# PSPS_AVNC_SRD_power-2020-10-23_FABRICATE.net
KiCad netlist of a schematic drawn in EAGLE
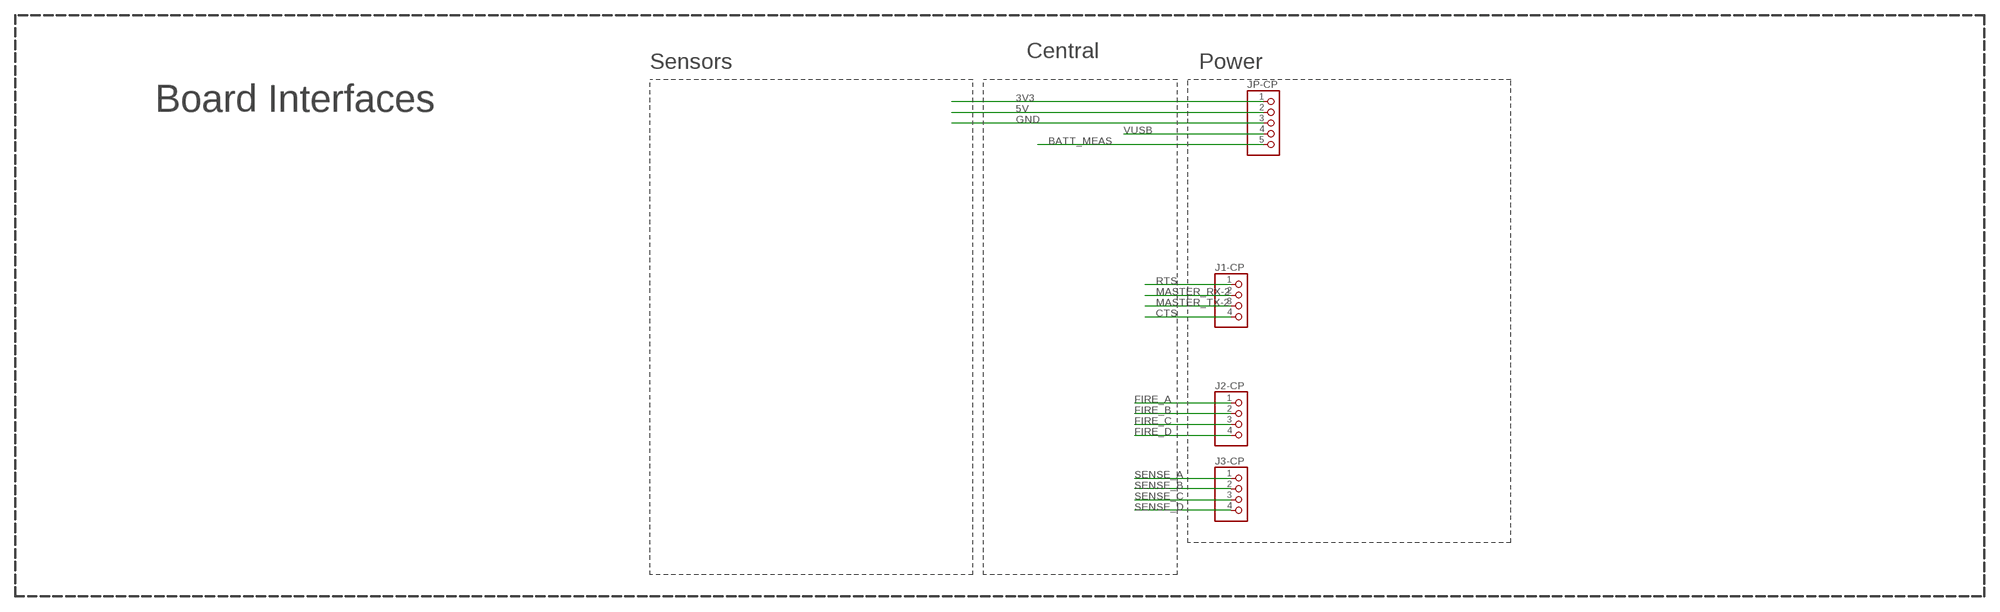
[diagram p0: schematic, sheet 1, part 1 of 3]
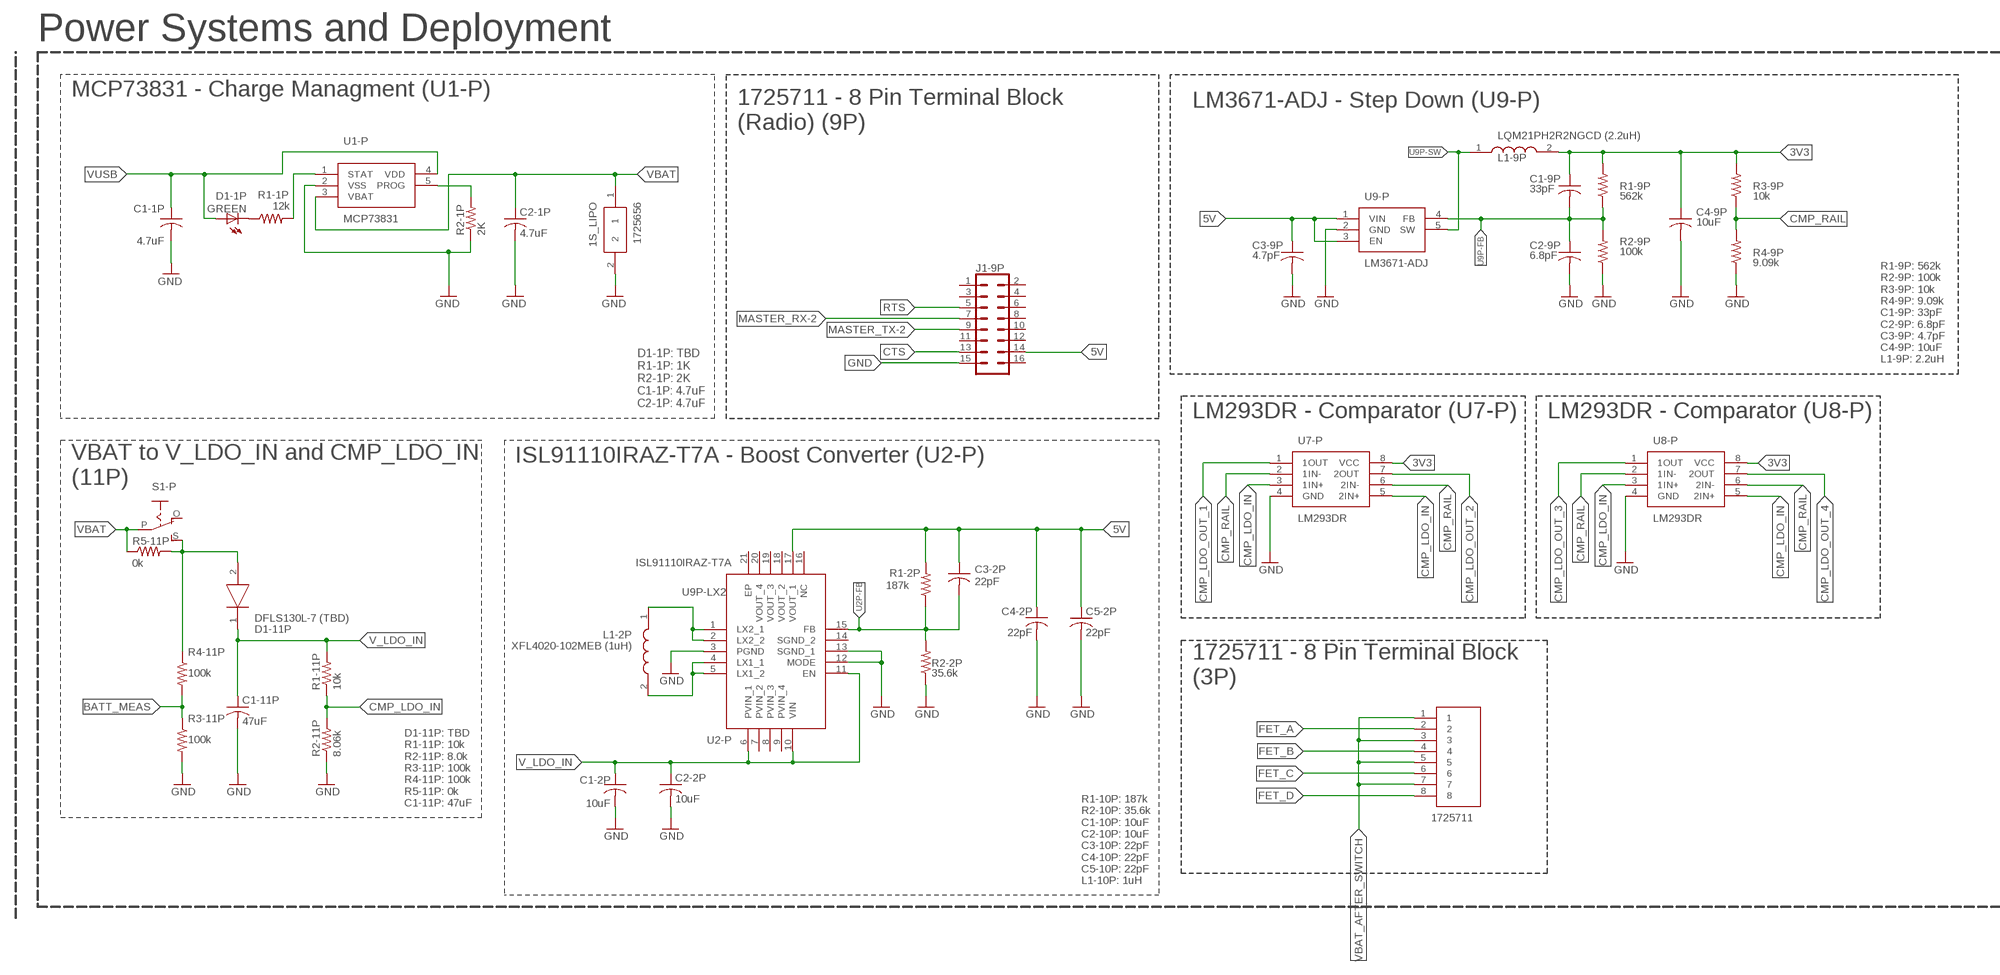
[diagram p1: schematic, sheet 1, part 2 of 3]
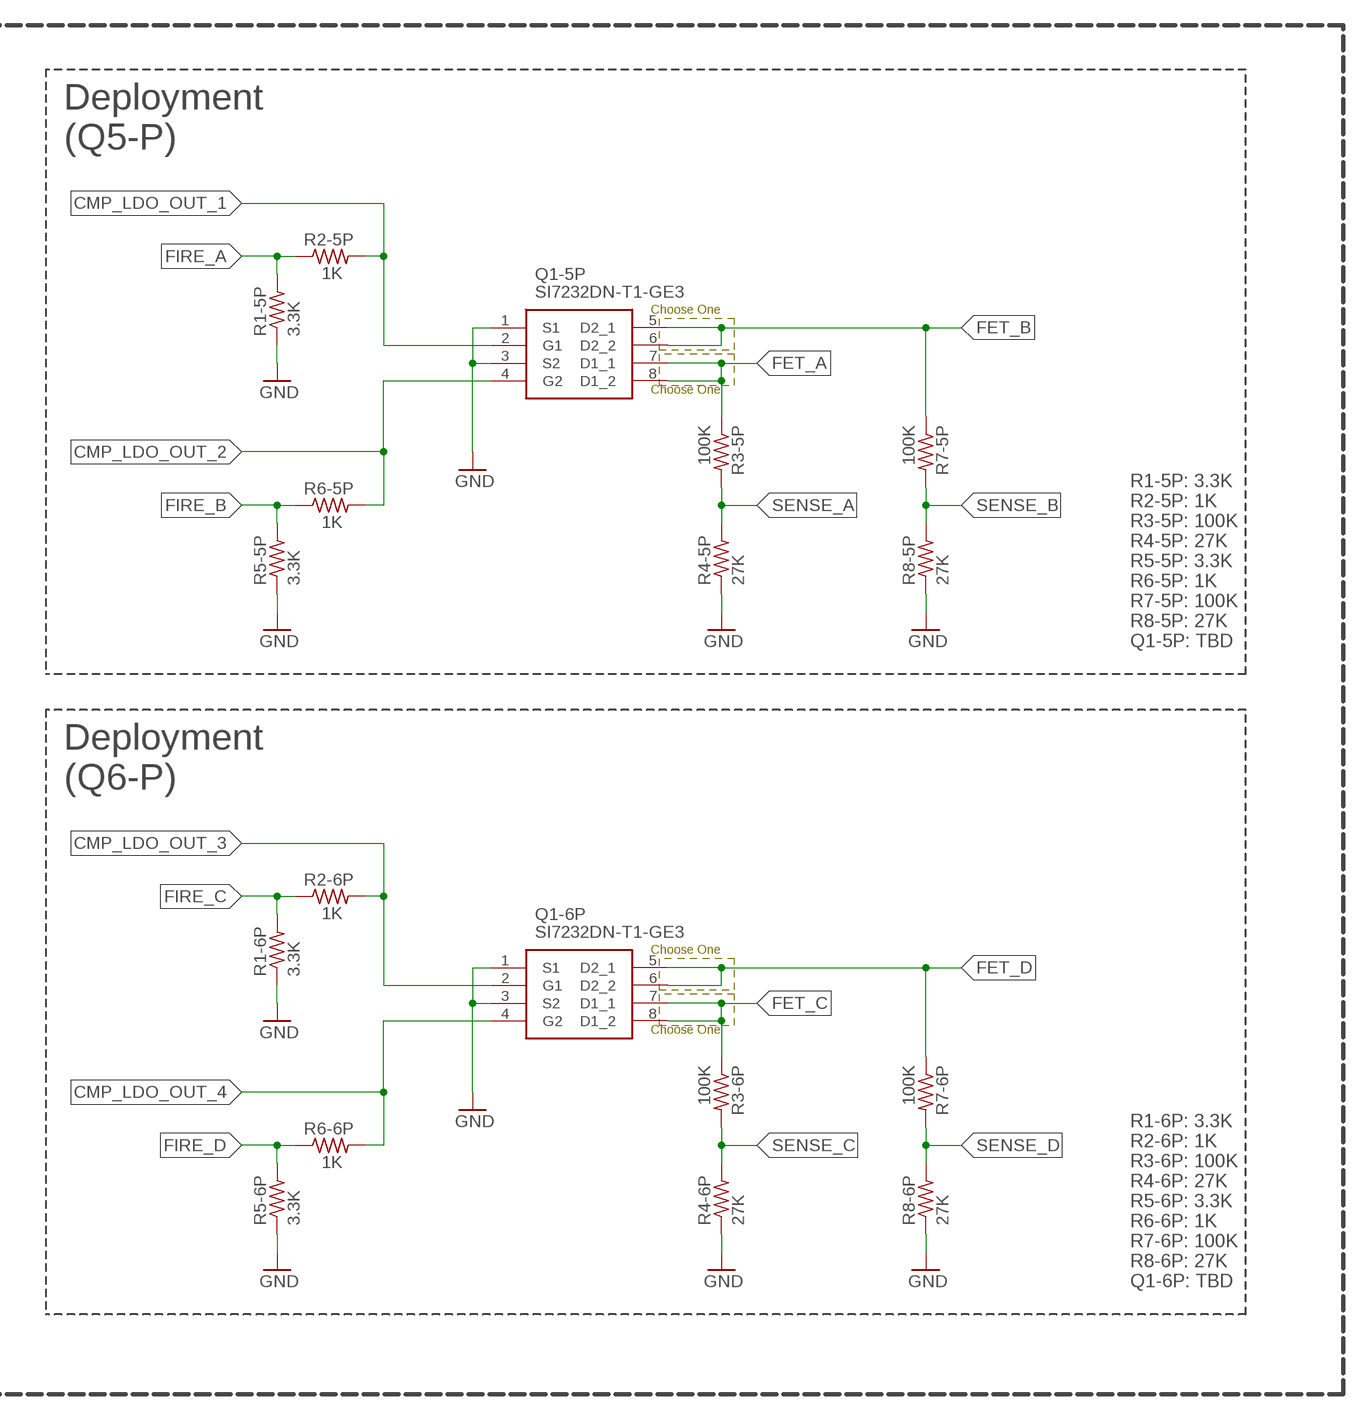
[diagram p2: schematic, sheet 1, part 3 of 3]

(export (version "E")
  (design (tool "Eeschema 10.0.6"))
  (components
    (comp (ref "1S_LIPO")
      (value "1725656")
      (footprint "eagle-import:1725656")
      (fields (field (name "MOUSER_PART_NUMBER") "651-1725656"))
      (libsource (lib "eagle-import") (part "1725656"))
    )
    (comp (ref "C1-1P")
      (value "4.7uF")
      (footprint "eagle-import:C0805")
      (libsource (lib "eagle-import") (part "resistor_348_C-USC0805"))
    )
    (comp (ref "C1-2P")
      (value "10uF")
      (footprint "eagle-import:C0805")
      (libsource (lib "eagle-import") (part "resistor_348_C-USC0805"))
    )
    (comp (ref "C1-9P")
      (value "33pF")
      (footprint "eagle-import:C0805")
      (libsource (lib "eagle-import") (part "resistor_348_C-USC0805"))
    )
    (comp (ref "C1-11P")
      (value "47uF")
      (footprint "eagle-import:C0805")
      (libsource (lib "eagle-import") (part "resistor_348_C-USC0805"))
    )
    (comp (ref "C2-1P")
      (value "4.7uF")
      (footprint "eagle-import:C0805")
      (libsource (lib "eagle-import") (part "resistor_348_C-USC0805"))
    )
    (comp (ref "C2-2P")
      (value "10uF")
      (footprint "eagle-import:C0805")
      (libsource (lib "eagle-import") (part "C-USC0805"))
    )
    (comp (ref "C2-9P")
      (value "6.8pF")
      (footprint "eagle-import:C0805")
      (libsource (lib "eagle-import") (part "resistor_348_C-USC0805"))
    )
    (comp (ref "C3-2P")
      (value "22pF")
      (footprint "eagle-import:C0805")
      (libsource (lib "eagle-import") (part "resistor_348_C-USC0805"))
    )
    (comp (ref "C3-9P")
      (value "4.7pF")
      (footprint "eagle-import:C0805")
      (libsource (lib "eagle-import") (part "resistor_348_C-USC0805"))
    )
    (comp (ref "C4-2P")
      (value "22pF")
      (footprint "eagle-import:C0805")
      (fields (field (name "SPICEPREFIX") "C"))
      (libsource (lib "eagle-import") (part "resistor_348_C-USC0805"))
    )
    (comp (ref "C4-9P")
      (value "10uF")
      (footprint "eagle-import:C0805")
      (libsource (lib "eagle-import") (part "resistor_348_C-USC0805"))
    )
    (comp (ref "C5-2P")
      (value "22pF")
      (footprint "eagle-import:C0805")
      (libsource (lib "eagle-import") (part "C-USC0805"))
    )
    (comp (ref "D1-1P")
      (value "GREEN")
      (footprint "eagle-import:CHIPLED_0805")
      (libsource (lib "eagle-import") (part "LEDCHIPLED_0805"))
    )
    (comp (ref "D1-11P")
      (value "DFLS130L-7 (TBD)")
      (footprint "eagle-import:POWERDI_123")
      (fields
        (field (name "MANUFACTURER_PART_NUMBER") "DFLS130L-7")
        (field (name "MOUSER_PART_NUMBER") "621-DFLS130L")
      )
      (libsource (lib "eagle-import") (part "DFLS130L-7"))
    )
    (comp (ref "J1-9P")
      (value "CONN_08X2")
      (footprint "eagle-import:2X8")
      (libsource (lib "eagle-import") (part "CONN_08X2"))
    )
    (comp (ref "J1-CP")
      (value "PINHD-1X4")
      (footprint "eagle-import:1X04")
      (libsource (lib "eagle-import") (part "PINHD-1X4"))
    )
    (comp (ref "J2-CP")
      (value "PINHD-1X4")
      (footprint "eagle-import:1X04")
      (libsource (lib "eagle-import") (part "PINHD-1X4"))
    )
    (comp (ref "J2-P")
      (value "1725711")
      (footprint "eagle-import:1725711")
      (fields (field (name "MOUSER_PART_NUMBER") "651-1725711"))
      (libsource (lib "eagle-import") (part "1725711"))
    )
    (comp (ref "J3-CP")
      (value "PINHD-1X4")
      (footprint "eagle-import:1X04")
      (libsource (lib "eagle-import") (part "PINHD-1X4"))
    )
    (comp (ref "JP-CP")
      (value "PINHD-1X5")
      (footprint "eagle-import:1X05")
      (libsource (lib "eagle-import") (part "PINHD-1X5"))
    )
    (comp (ref "L1-2P")
      (value "XFL4020-102MEB (1uH)")
      (footprint "eagle-import:XFL4020")
      (fields
        (field (name "MANUFACTURER_PART_NUMBER") "XFL4020-102MEB")
        (field (name "MOUSER_PART_NUMBER") "994-XFL4020-102MEB")
      )
      (libsource (lib "eagle-import") (part "XFL4020-102MEB"))
    )
    (comp (ref "L1-9P")
      (value "LQM21PH2R2NGCD (2.2uH)")
      (footprint "eagle-import:INDC2012X100N")
      (fields
        (field (name "MANUFACTURER_PART_NUMBER") "LQM21PH2R2NGCD")
        (field (name "MOUSER_PART_NUMBER") "81-LQM21PH2R2NGCD")
      )
      (libsource (lib "eagle-import") (part "LQM21PH2R2NGCD"))
    )
    (comp (ref "Q1-5P")
      (value "SI7232DN-T1-GE3")
      (footprint "eagle-import:POWERPAK-1212-8")
      (fields (field (name "MOUSER_PART_NUMBER") "781-SI7232DN-GE3"))
      (libsource (lib "eagle-import") (part "SI7232DN-T1-GE3"))
    )
    (comp (ref "Q1-6P")
      (value "SI7232DN-T1-GE3")
      (footprint "eagle-import:POWERPAK-1212-8")
      (fields (field (name "MOUSER_PART_NUMBER") "781-SI7232DN-GE3"))
      (libsource (lib "eagle-import") (part "SI7232DN-T1-GE3"))
    )
    (comp (ref "R1-1P")
      (value "12k")
      (footprint "eagle-import:R0805")
      (libsource (lib "eagle-import") (part "resistor_348_R-US_R0805"))
    )
    (comp (ref "R1-2P")
      (value "187k")
      (footprint "eagle-import:R0805")
      (libsource (lib "eagle-import") (part "resistor_348_R-US_R0805"))
    )
    (comp (ref "R1-5P")
      (value "3.3K")
      (footprint "eagle-import:M0805")
      (libsource (lib "eagle-import") (part "rcl_334_R-US_M0805"))
    )
    (comp (ref "R1-6P")
      (value "3.3K")
      (footprint "eagle-import:M0805")
      (libsource (lib "eagle-import") (part "rcl_334_R-US_M0805"))
    )
    (comp (ref "R1-9P")
      (value "562k")
      (footprint "eagle-import:R0805")
      (libsource (lib "eagle-import") (part "resistor_348_R-US_R0805"))
    )
    (comp (ref "R1-11P")
      (value "10k")
      (footprint "eagle-import:R0805")
      (libsource (lib "eagle-import") (part "resistor_348_R-US_R0805"))
    )
    (comp (ref "R2-1P")
      (value "2K")
      (footprint "eagle-import:R0805")
      (libsource (lib "eagle-import") (part "resistor_348_R-US_R0805"))
    )
    (comp (ref "R2-2P")
      (value "35.6k")
      (footprint "eagle-import:R0805")
      (libsource (lib "eagle-import") (part "resistor_348_R-US_R0805"))
    )
    (comp (ref "R2-5P")
      (value "1K")
      (footprint "eagle-import:M0805")
      (libsource (lib "eagle-import") (part "rcl_334_R-US_M0805"))
    )
    (comp (ref "R2-6P")
      (value "1K")
      (footprint "eagle-import:M0805")
      (libsource (lib "eagle-import") (part "rcl_334_R-US_M0805"))
    )
    (comp (ref "R2-9P")
      (value "100k")
      (footprint "eagle-import:R0805")
      (libsource (lib "eagle-import") (part "resistor_348_R-US_R0805"))
    )
    (comp (ref "R2-11P")
      (value "8.06k")
      (footprint "eagle-import:R0805")
      (libsource (lib "eagle-import") (part "resistor_348_R-US_R0805"))
    )
    (comp (ref "R3-5P")
      (value "100K")
      (footprint "eagle-import:M0805")
      (libsource (lib "eagle-import") (part "rcl_334_R-US_M0805"))
    )
    (comp (ref "R3-6P")
      (value "100K")
      (footprint "eagle-import:M0805")
      (libsource (lib "eagle-import") (part "rcl_334_R-US_M0805"))
    )
    (comp (ref "R3-9P")
      (value "10k")
      (footprint "eagle-import:R0805")
      (libsource (lib "eagle-import") (part "resistor_348_R-US_R0805"))
    )
    (comp (ref "R3-11P")
      (value "100k")
      (footprint "eagle-import:R0805")
      (libsource (lib "eagle-import") (part "R-US_R0805"))
    )
    (comp (ref "R4-5P")
      (value "27K")
      (footprint "eagle-import:M0805")
      (libsource (lib "eagle-import") (part "rcl_334_R-US_M0805"))
    )
    (comp (ref "R4-6P")
      (value "27K")
      (footprint "eagle-import:M0805")
      (libsource (lib "eagle-import") (part "rcl_334_R-US_M0805"))
    )
    (comp (ref "R4-9P")
      (value "9.09k")
      (footprint "eagle-import:R0805")
      (libsource (lib "eagle-import") (part "resistor_348_R-US_R0805"))
    )
    (comp (ref "R4-11P")
      (value "100k")
      (footprint "eagle-import:R0805")
      (libsource (lib "eagle-import") (part "R-US_R0805"))
    )
    (comp (ref "R5-5P")
      (value "3.3K")
      (footprint "eagle-import:M0805")
      (libsource (lib "eagle-import") (part "rcl_334_R-US_M0805"))
    )
    (comp (ref "R5-6P")
      (value "3.3K")
      (footprint "eagle-import:M0805")
      (libsource (lib "eagle-import") (part "rcl_334_R-US_M0805"))
    )
    (comp (ref "R5-11P")
      (value "0k")
      (footprint "eagle-import:R0805")
      (libsource (lib "eagle-import") (part "R-US_R0805"))
    )
    (comp (ref "R6-5P")
      (value "1K")
      (footprint "eagle-import:M0805")
      (libsource (lib "eagle-import") (part "rcl_334_R-US_M0805"))
    )
    (comp (ref "R6-6P")
      (value "1K")
      (footprint "eagle-import:M0805")
      (libsource (lib "eagle-import") (part "rcl_334_R-US_M0805"))
    )
    (comp (ref "R7-5P")
      (value "100K")
      (footprint "eagle-import:M0805")
      (libsource (lib "eagle-import") (part "rcl_334_R-US_M0805"))
    )
    (comp (ref "R7-6P")
      (value "100K")
      (footprint "eagle-import:M0805")
      (libsource (lib "eagle-import") (part "rcl_334_R-US_M0805"))
    )
    (comp (ref "R8-5P")
      (value "27K")
      (footprint "eagle-import:M0805")
      (libsource (lib "eagle-import") (part "rcl_334_R-US_M0805"))
    )
    (comp (ref "R8-6P")
      (value "27K")
      (footprint "eagle-import:M0805")
      (libsource (lib "eagle-import") (part "rcl_334_R-US_M0805"))
    )
    (comp (ref "S1-P")
      (value "EG1218S")
      (footprint "eagle-import:EG1218")
      (libsource (lib "eagle-import") (part "EG1218S"))
    )
    (comp (ref "U1-P")
      (value "MCP73831")
      (footprint "eagle-import:SOT95P270X145-5N")
      (fields
        (field (name "MANUFACTURER_PART_NUMBER") "MCP73831T-2ACI/OT")
        (field (name "MOUSER_PART_NUMBER") "579-MCP73831T-2ACIOT")
      )
      (libsource (lib "eagle-import") (part "MCP73831T-2ACI_OT"))
    )
    (comp (ref "U2-P")
      (value "ISL91110IRAZ-T7A")
      (footprint "eagle-import:QFN50P400X400X100-21N")
      (libsource (lib "eagle-import") (part "ISL91110IRAZ-T7A"))
    )
    (comp (ref "U7-P")
      (value "LM293DR")
      (footprint "eagle-import:SOIC127P600X175-8N")
      (fields (field (name "MOUSER_PART_NUMBER") "595-LM293DR"))
      (libsource (lib "eagle-import") (part "LM293DR"))
    )
    (comp (ref "U8-P")
      (value "LM293DR")
      (footprint "eagle-import:SOIC127P600X175-8N")
      (fields (field (name "MOUSER_PART_NUMBER") "595-LM293DR"))
      (libsource (lib "eagle-import") (part "LM293DR"))
    )
    (comp (ref "U9-P")
      (value "LM3671-ADJ")
      (footprint "eagle-import:SOT95P280X145-5N")
      (fields
        (field (name "MANUFACTURER_PART_NUMBER") "LM3671MFX-ADJ/NOPB")
        (field (name "MOUSER_PART_NUMBER") "926-LM3671MFXADJNOPB")
      )
      (libsource (lib "eagle-import") (part "LM3671MFX-ADJ_NOPB"))
    )
  )
  (nets
    (net (code "1") (name "/U9P-LX2") (class "Default")
      (node (ref "L1-2P") (pin "1") (pinfunction "1_1") (pintype "bidirectional"))
      (node (ref "U2-P") (pin "1") (pinfunction "LX2_1_1") (pintype "bidirectional"))
      (node (ref "U2-P") (pin "2") (pinfunction "LX2_2_2") (pintype "bidirectional"))
    )
    (net (code "2") (name "3V3") (class "Default")
      (node (ref "C1-9P") (pin "1") (pinfunction "1_1") (pintype "passive"))
      (node (ref "C4-9P") (pin "1") (pinfunction "1_1") (pintype "passive"))
      (node (ref "JP-CP") (pin "1") (pinfunction "1_1") (pintype "passive"))
      (node (ref "L1-9P") (pin "2") (pinfunction "2_2") (pintype "bidirectional"))
      (node (ref "R1-9P") (pin "2") (pinfunction "2_2") (pintype "passive"))
      (node (ref "R3-9P") (pin "2") (pinfunction "2_2") (pintype "passive"))
      (node (ref "U7-P") (pin "8") (pinfunction "VCC_8") (pintype "bidirectional"))
      (node (ref "U8-P") (pin "8") (pinfunction "VCC_8") (pintype "bidirectional"))
    )
    (net (code "3") (name "5V") (class "Default")
      (node (ref "C3-2P") (pin "1") (pinfunction "1_1") (pintype "passive"))
      (node (ref "C3-9P") (pin "1") (pinfunction "1_1") (pintype "passive"))
      (node (ref "C4-2P") (pin "1") (pinfunction "1_1") (pintype "passive"))
      (node (ref "C5-2P") (pin "1") (pinfunction "1_1") (pintype "passive"))
      (node (ref "J1-9P") (pin "14") (pinfunction "14_14") (pintype "passive"))
      (node (ref "JP-CP") (pin "2") (pinfunction "2_2") (pintype "passive"))
      (node (ref "R1-2P") (pin "2") (pinfunction "2_2") (pintype "passive"))
      (node (ref "U2-P") (pin "17") (pinfunction "VOUT_1_17") (pintype "bidirectional"))
      (node (ref "U9-P") (pin "1") (pinfunction "VIN_1") (pintype "bidirectional"))
      (node (ref "U9-P") (pin "3") (pinfunction "EN_3") (pintype "bidirectional"))
    )
    (net (code "4") (name "BATT_MEAS") (class "Default")
      (node (ref "JP-CP") (pin "5") (pinfunction "5_5") (pintype "passive"))
      (node (ref "R3-11P") (pin "1") (pinfunction "1_1") (pintype "passive"))
      (node (ref "R4-11P") (pin "2") (pinfunction "2_2") (pintype "passive"))
    )
    (net (code "5") (name "CMP_LDO_IN") (class "Default")
      (node (ref "R1-11P") (pin "1") (pinfunction "1_1") (pintype "passive"))
      (node (ref "R2-11P") (pin "2") (pinfunction "2_2") (pintype "passive"))
      (node (ref "U7-P") (pin "3") (pinfunction "1IN+_3") (pintype "bidirectional"))
      (node (ref "U7-P") (pin "5") (pinfunction "2IN+_5") (pintype "bidirectional"))
      (node (ref "U8-P") (pin "3") (pinfunction "1IN+_3") (pintype "bidirectional"))
      (node (ref "U8-P") (pin "5") (pinfunction "2IN+_5") (pintype "bidirectional"))
    )
    (net (code "6") (name "CMP_LDO_OUT_1") (class "Default")
      (node (ref "Q1-5P") (pin "2") (pinfunction "G1_2") (pintype "bidirectional"))
      (node (ref "R2-5P") (pin "2") (pinfunction "2_2") (pintype "passive"))
      (node (ref "U7-P") (pin "1") (pinfunction "1OUT_1") (pintype "bidirectional"))
    )
    (net (code "7") (name "CMP_LDO_OUT_2") (class "Default")
      (node (ref "Q1-5P") (pin "4") (pinfunction "G2_4") (pintype "bidirectional"))
      (node (ref "R6-5P") (pin "2") (pinfunction "2_2") (pintype "passive"))
      (node (ref "U7-P") (pin "7") (pinfunction "2OUT_7") (pintype "bidirectional"))
    )
    (net (code "8") (name "CMP_LDO_OUT_3") (class "Default")
      (node (ref "Q1-6P") (pin "2") (pinfunction "G1_2") (pintype "bidirectional"))
      (node (ref "R2-6P") (pin "2") (pinfunction "2_2") (pintype "passive"))
      (node (ref "U8-P") (pin "1") (pinfunction "1OUT_1") (pintype "bidirectional"))
    )
    (net (code "9") (name "CMP_LDO_OUT_4") (class "Default")
      (node (ref "Q1-6P") (pin "4") (pinfunction "G2_4") (pintype "bidirectional"))
      (node (ref "R6-6P") (pin "2") (pinfunction "2_2") (pintype "passive"))
      (node (ref "U8-P") (pin "7") (pinfunction "2OUT_7") (pintype "bidirectional"))
    )
    (net (code "10") (name "CMP_RAIL") (class "Default")
      (node (ref "R3-9P") (pin "1") (pinfunction "1_1") (pintype "passive"))
      (node (ref "R4-9P") (pin "2") (pinfunction "2_2") (pintype "passive"))
      (node (ref "U7-P") (pin "2") (pinfunction "1IN-_2") (pintype "bidirectional"))
      (node (ref "U7-P") (pin "6") (pinfunction "2IN-_6") (pintype "bidirectional"))
      (node (ref "U8-P") (pin "2") (pinfunction "1IN-_2") (pintype "bidirectional"))
      (node (ref "U8-P") (pin "6") (pinfunction "2IN-_6") (pintype "bidirectional"))
    )
    (net (code "11") (name "CTS") (class "Default")
      (node (ref "J1-9P") (pin "13") (pinfunction "13_13") (pintype "passive"))
      (node (ref "J1-CP") (pin "4") (pinfunction "4_4") (pintype "passive"))
    )
    (net (code "12") (name "FET_A") (class "Default")
      (node (ref "J2-P") (pin "2") (pinfunction "2_2") (pintype "bidirectional"))
      (node (ref "Q1-5P") (pin "7") (pinfunction "D1_1_7") (pintype "bidirectional"))
      (node (ref "Q1-5P") (pin "8") (pinfunction "D1_2_8") (pintype "bidirectional"))
      (node (ref "R3-5P") (pin "1") (pinfunction "1_1") (pintype "passive"))
    )
    (net (code "13") (name "FET_B") (class "Default")
      (node (ref "J2-P") (pin "4") (pinfunction "4_4") (pintype "bidirectional"))
      (node (ref "Q1-5P") (pin "5") (pinfunction "D2_1_5") (pintype "bidirectional"))
      (node (ref "Q1-5P") (pin "6") (pinfunction "D2_2_6") (pintype "bidirectional"))
      (node (ref "R7-5P") (pin "1") (pinfunction "1_1") (pintype "passive"))
    )
    (net (code "14") (name "FET_C") (class "Default")
      (node (ref "J2-P") (pin "6") (pinfunction "6_6") (pintype "bidirectional"))
      (node (ref "Q1-6P") (pin "7") (pinfunction "D1_1_7") (pintype "bidirectional"))
      (node (ref "Q1-6P") (pin "8") (pinfunction "D1_2_8") (pintype "bidirectional"))
      (node (ref "R3-6P") (pin "1") (pinfunction "1_1") (pintype "passive"))
    )
    (net (code "15") (name "FET_D") (class "Default")
      (node (ref "J2-P") (pin "8") (pinfunction "8_8") (pintype "bidirectional"))
      (node (ref "Q1-6P") (pin "5") (pinfunction "D2_1_5") (pintype "bidirectional"))
      (node (ref "Q1-6P") (pin "6") (pinfunction "D2_2_6") (pintype "bidirectional"))
      (node (ref "R7-6P") (pin "1") (pinfunction "1_1") (pintype "passive"))
    )
    (net (code "16") (name "FIRE_A") (class "Default")
      (node (ref "J2-CP") (pin "1") (pinfunction "1_1") (pintype "passive"))
      (node (ref "R1-5P") (pin "2") (pinfunction "2_2") (pintype "passive"))
      (node (ref "R2-5P") (pin "1") (pinfunction "1_1") (pintype "passive"))
    )
    (net (code "17") (name "FIRE_B") (class "Default")
      (node (ref "J2-CP") (pin "2") (pinfunction "2_2") (pintype "passive"))
      (node (ref "R5-5P") (pin "2") (pinfunction "2_2") (pintype "passive"))
      (node (ref "R6-5P") (pin "1") (pinfunction "1_1") (pintype "passive"))
    )
    (net (code "18") (name "FIRE_C") (class "Default")
      (node (ref "J2-CP") (pin "3") (pinfunction "3_3") (pintype "passive"))
      (node (ref "R1-6P") (pin "2") (pinfunction "2_2") (pintype "passive"))
      (node (ref "R2-6P") (pin "1") (pinfunction "1_1") (pintype "passive"))
    )
    (net (code "19") (name "FIRE_D") (class "Default")
      (node (ref "J2-CP") (pin "4") (pinfunction "4_4") (pintype "passive"))
      (node (ref "R5-6P") (pin "2") (pinfunction "2_2") (pintype "passive"))
      (node (ref "R6-6P") (pin "1") (pinfunction "1_1") (pintype "passive"))
    )
    (net (code "20") (name "GND") (class "Default")
      (node (ref "1S_LIPO") (pin "2") (pinfunction "2_2") (pintype "bidirectional"))
      (node (ref "C1-11P") (pin "2") (pinfunction "2_2") (pintype "passive"))
      (node (ref "C1-1P") (pin "2") (pinfunction "2_2") (pintype "passive"))
      (node (ref "C1-2P") (pin "2") (pinfunction "2_2") (pintype "passive"))
      (node (ref "C2-1P") (pin "2") (pinfunction "2_2") (pintype "passive"))
      (node (ref "C2-2P") (pin "2") (pinfunction "2_2") (pintype "passive"))
      (node (ref "C2-9P") (pin "2") (pinfunction "2_2") (pintype "passive"))
      (node (ref "C3-9P") (pin "2") (pinfunction "2_2") (pintype "passive"))
      (node (ref "C4-2P") (pin "2") (pinfunction "2_2") (pintype "passive"))
      (node (ref "C4-9P") (pin "2") (pinfunction "2_2") (pintype "passive"))
      (node (ref "C5-2P") (pin "2") (pinfunction "2_2") (pintype "passive"))
      (node (ref "J1-9P") (pin "15") (pinfunction "15_15") (pintype "passive"))
      (node (ref "JP-CP") (pin "3") (pinfunction "3_3") (pintype "passive"))
      (node (ref "Q1-5P") (pin "1") (pinfunction "S1_1") (pintype "bidirectional"))
      (node (ref "Q1-5P") (pin "3") (pinfunction "S2_3") (pintype "bidirectional"))
      (node (ref "Q1-6P") (pin "1") (pinfunction "S1_1") (pintype "bidirectional"))
      (node (ref "Q1-6P") (pin "3") (pinfunction "S2_3") (pintype "bidirectional"))
      (node (ref "R1-5P") (pin "1") (pinfunction "1_1") (pintype "passive"))
      (node (ref "R1-6P") (pin "1") (pinfunction "1_1") (pintype "passive"))
      (node (ref "R2-11P") (pin "1") (pinfunction "1_1") (pintype "passive"))
      (node (ref "R2-1P") (pin "1") (pinfunction "1_1") (pintype "passive"))
      (node (ref "R2-2P") (pin "1") (pinfunction "1_1") (pintype "passive"))
      (node (ref "R2-9P") (pin "1") (pinfunction "1_1") (pintype "passive"))
      (node (ref "R3-11P") (pin "2") (pinfunction "2_2") (pintype "passive"))
      (node (ref "R4-5P") (pin "1") (pinfunction "1_1") (pintype "passive"))
      (node (ref "R4-6P") (pin "1") (pinfunction "1_1") (pintype "passive"))
      (node (ref "R4-9P") (pin "1") (pinfunction "1_1") (pintype "passive"))
      (node (ref "R5-5P") (pin "1") (pinfunction "1_1") (pintype "passive"))
      (node (ref "R5-6P") (pin "1") (pinfunction "1_1") (pintype "passive"))
      (node (ref "R8-5P") (pin "1") (pinfunction "1_1") (pintype "passive"))
      (node (ref "R8-6P") (pin "1") (pinfunction "1_1") (pintype "passive"))
      (node (ref "U1-P") (pin "2") (pinfunction "VSS_2") (pintype "bidirectional"))
      (node (ref "U2-P") (pin "12") (pinfunction "MODE_12") (pintype "bidirectional"))
      (node (ref "U2-P") (pin "13") (pinfunction "SGND_1_13") (pintype "bidirectional"))
      (node (ref "U2-P") (pin "3") (pinfunction "PGND_3") (pintype "bidirectional"))
      (node (ref "U7-P") (pin "4") (pinfunction "GND_4") (pintype "bidirectional"))
      (node (ref "U8-P") (pin "4") (pinfunction "GND_4") (pintype "bidirectional"))
      (node (ref "U9-P") (pin "2") (pinfunction "GND_2") (pintype "bidirectional"))
    )
    (net (code "21") (name "MASTER_RX-2") (class "Default")
      (node (ref "J1-9P") (pin "7") (pinfunction "7_7") (pintype "passive"))
      (node (ref "J1-CP") (pin "2") (pinfunction "2_2") (pintype "passive"))
    )
    (net (code "22") (name "MASTER_TX-2") (class "Default")
      (node (ref "J1-9P") (pin "9") (pinfunction "9_9") (pintype "passive"))
      (node (ref "J1-CP") (pin "3") (pinfunction "3_3") (pintype "passive"))
    )
    (net (code "23") (name "Net-(D1-1P-PadC)") (class "Default")
      (node (ref "D1-1P") (pin "C") (pinfunction "C_C") (pintype "passive"))
      (node (ref "R1-1P") (pin "1") (pinfunction "1_1") (pintype "passive"))
    )
    (net (code "24") (name "Net-(U1-P-PROG)") (class "Default")
      (node (ref "R2-1P") (pin "2") (pinfunction "2_2") (pintype "passive"))
      (node (ref "U1-P") (pin "5") (pinfunction "PROG_5") (pintype "bidirectional"))
    )
    (net (code "25") (name "Net-(U1-P-STAT)") (class "Default")
      (node (ref "R1-1P") (pin "2") (pinfunction "2_2") (pintype "passive"))
      (node (ref "U1-P") (pin "1") (pinfunction "STAT_1") (pintype "bidirectional"))
    )
    (net (code "26") (name "Net-(U2-P-LX1_1)") (class "Default")
      (node (ref "L1-2P") (pin "2") (pinfunction "2_2") (pintype "bidirectional"))
      (node (ref "U2-P") (pin "4") (pinfunction "LX1_1_4") (pintype "bidirectional"))
      (node (ref "U2-P") (pin "5") (pinfunction "LX1_2_5") (pintype "bidirectional"))
    )
    (net (code "27") (name "RTS") (class "Default")
      (node (ref "J1-9P") (pin "5") (pinfunction "5_5") (pintype "passive"))
      (node (ref "J1-CP") (pin "1") (pinfunction "1_1") (pintype "passive"))
    )
    (net (code "28") (name "SENSE_A") (class "Default")
      (node (ref "J3-CP") (pin "1") (pinfunction "1_1") (pintype "passive"))
      (node (ref "R3-5P") (pin "2") (pinfunction "2_2") (pintype "passive"))
      (node (ref "R4-5P") (pin "2") (pinfunction "2_2") (pintype "passive"))
    )
    (net (code "29") (name "SENSE_B") (class "Default")
      (node (ref "J3-CP") (pin "2") (pinfunction "2_2") (pintype "passive"))
      (node (ref "R7-5P") (pin "2") (pinfunction "2_2") (pintype "passive"))
      (node (ref "R8-5P") (pin "2") (pinfunction "2_2") (pintype "passive"))
    )
    (net (code "30") (name "SENSE_C") (class "Default")
      (node (ref "J3-CP") (pin "3") (pinfunction "3_3") (pintype "passive"))
      (node (ref "R3-6P") (pin "2") (pinfunction "2_2") (pintype "passive"))
      (node (ref "R4-6P") (pin "2") (pinfunction "2_2") (pintype "passive"))
    )
    (net (code "31") (name "SENSE_D") (class "Default")
      (node (ref "J3-CP") (pin "4") (pinfunction "4_4") (pintype "passive"))
      (node (ref "R7-6P") (pin "2") (pinfunction "2_2") (pintype "passive"))
      (node (ref "R8-6P") (pin "2") (pinfunction "2_2") (pintype "passive"))
    )
    (net (code "32") (name "U2P-FB") (class "Default")
      (node (ref "C3-2P") (pin "2") (pinfunction "2_2") (pintype "passive"))
      (node (ref "R1-2P") (pin "1") (pinfunction "1_1") (pintype "passive"))
      (node (ref "R2-2P") (pin "2") (pinfunction "2_2") (pintype "passive"))
      (node (ref "U2-P") (pin "15") (pinfunction "FB_15") (pintype "bidirectional"))
    )
    (net (code "33") (name "U9P-FB") (class "Default")
      (node (ref "C1-9P") (pin "2") (pinfunction "2_2") (pintype "passive"))
      (node (ref "C2-9P") (pin "1") (pinfunction "1_1") (pintype "passive"))
      (node (ref "R1-9P") (pin "1") (pinfunction "1_1") (pintype "passive"))
      (node (ref "R2-9P") (pin "2") (pinfunction "2_2") (pintype "passive"))
      (node (ref "U9-P") (pin "4") (pinfunction "FB_4") (pintype "bidirectional"))
    )
    (net (code "34") (name "U9P-SW") (class "Default")
      (node (ref "L1-9P") (pin "1") (pinfunction "1_1") (pintype "bidirectional"))
      (node (ref "U9-P") (pin "5") (pinfunction "SW_5") (pintype "bidirectional"))
    )
    (net (code "35") (name "VBAT") (class "Default")
      (node (ref "1S_LIPO") (pin "1") (pinfunction "1_1") (pintype "bidirectional"))
      (node (ref "C2-1P") (pin "1") (pinfunction "1_1") (pintype "passive"))
      (node (ref "R5-11P") (pin "1") (pinfunction "1_1") (pintype "passive"))
      (node (ref "S1-P") (pin "P") (pinfunction "P_P") (pintype "passive"))
      (node (ref "U1-P") (pin "3") (pinfunction "VBAT_3") (pintype "bidirectional"))
    )
    (net (code "36") (name "VBAT_AFTER_SWITCH") (class "Default")
      (node (ref "D1-11P") (pin "2") (pinfunction "A_2") (pintype "bidirectional"))
      (node (ref "J2-P") (pin "1") (pinfunction "1_1") (pintype "bidirectional"))
      (node (ref "J2-P") (pin "3") (pinfunction "3_3") (pintype "bidirectional"))
      (node (ref "J2-P") (pin "5") (pinfunction "5_5") (pintype "bidirectional"))
      (node (ref "J2-P") (pin "7") (pinfunction "7_7") (pintype "bidirectional"))
      (node (ref "R4-11P") (pin "1") (pinfunction "1_1") (pintype "passive"))
      (node (ref "R5-11P") (pin "2") (pinfunction "2_2") (pintype "passive"))
      (node (ref "S1-P") (pin "S") (pinfunction "S_S") (pintype "passive"))
    )
    (net (code "37") (name "VUSB") (class "Default")
      (node (ref "C1-1P") (pin "1") (pinfunction "1_1") (pintype "passive"))
      (node (ref "D1-1P") (pin "A") (pinfunction "A_A") (pintype "passive"))
      (node (ref "JP-CP") (pin "4") (pinfunction "4_4") (pintype "passive"))
      (node (ref "U1-P") (pin "4") (pinfunction "VDD_4") (pintype "bidirectional"))
    )
    (net (code "38") (name "V_LDO_IN") (class "Default")
      (node (ref "C1-11P") (pin "1") (pinfunction "1_1") (pintype "passive"))
      (node (ref "C1-2P") (pin "1") (pinfunction "1_1") (pintype "passive"))
      (node (ref "C2-2P") (pin "1") (pinfunction "1_1") (pintype "passive"))
      (node (ref "D1-11P") (pin "1") (pinfunction "K_1") (pintype "bidirectional"))
      (node (ref "R1-11P") (pin "2") (pinfunction "2_2") (pintype "passive"))
      (node (ref "U2-P") (pin "10") (pinfunction "VIN_10") (pintype "bidirectional"))
      (node (ref "U2-P") (pin "11") (pinfunction "EN_11") (pintype "bidirectional"))
      (node (ref "U2-P") (pin "6") (pinfunction "PVIN_1_6") (pintype "bidirectional"))
    )
    (net (code "39") (name "unconnected-(J1-9P-Pad1)") (class "Default")
      (node (ref "J1-9P") (pin "1") (pinfunction "1_1") (pintype "passive"))
    )
    (net (code "40") (name "unconnected-(J1-9P-Pad2)") (class "Default")
      (node (ref "J1-9P") (pin "2") (pinfunction "2_2") (pintype "passive"))
    )
    (net (code "41") (name "unconnected-(J1-9P-Pad3)") (class "Default")
      (node (ref "J1-9P") (pin "3") (pinfunction "3_3") (pintype "passive"))
    )
    (net (code "42") (name "unconnected-(J1-9P-Pad4)") (class "Default")
      (node (ref "J1-9P") (pin "4") (pinfunction "4_4") (pintype "passive"))
    )
    (net (code "43") (name "unconnected-(J1-9P-Pad6)") (class "Default")
      (node (ref "J1-9P") (pin "6") (pinfunction "6_6") (pintype "passive"))
    )
    (net (code "44") (name "unconnected-(J1-9P-Pad8)") (class "Default")
      (node (ref "J1-9P") (pin "8") (pinfunction "8_8") (pintype "passive"))
    )
    (net (code "45") (name "unconnected-(J1-9P-Pad10)") (class "Default")
      (node (ref "J1-9P") (pin "10") (pinfunction "10_10") (pintype "passive"))
    )
    (net (code "46") (name "unconnected-(J1-9P-Pad11)") (class "Default")
      (node (ref "J1-9P") (pin "11") (pinfunction "11_11") (pintype "passive"))
    )
    (net (code "47") (name "unconnected-(J1-9P-Pad12)") (class "Default")
      (node (ref "J1-9P") (pin "12") (pinfunction "12_12") (pintype "passive"))
    )
    (net (code "48") (name "unconnected-(J1-9P-Pad16)") (class "Default")
      (node (ref "J1-9P") (pin "16") (pinfunction "16_16") (pintype "passive"))
    )
    (net (code "49") (name "unconnected-(S1-P-PadO)") (class "Default")
      (node (ref "S1-P") (pin "O") (pinfunction "O_O") (pintype "passive"))
    )
    (net (code "50") (name "unconnected-(U2-P-EP-Pad21)") (class "Default")
      (node (ref "U2-P") (pin "21") (pinfunction "EP_21") (pintype "bidirectional"))
    )
    (net (code "51") (name "unconnected-(U2-P-NC-Pad16)") (class "Default")
      (node (ref "U2-P") (pin "16") (pinfunction "NC_16") (pintype "no_connect"))
    )
    (net (code "52") (name "unconnected-(U2-P-PVIN_2-Pad7)") (class "Default")
      (node (ref "U2-P") (pin "7") (pinfunction "PVIN_2_7") (pintype "bidirectional"))
    )
    (net (code "53") (name "unconnected-(U2-P-PVIN_3-Pad8)") (class "Default")
      (node (ref "U2-P") (pin "8") (pinfunction "PVIN_3_8") (pintype "bidirectional"))
    )
    (net (code "54") (name "unconnected-(U2-P-PVIN_4-Pad9)") (class "Default")
      (node (ref "U2-P") (pin "9") (pinfunction "PVIN_4_9") (pintype "bidirectional"))
    )
    (net (code "55") (name "unconnected-(U2-P-SGND_2-Pad14)") (class "Default")
      (node (ref "U2-P") (pin "14") (pinfunction "SGND_2_14") (pintype "bidirectional"))
    )
    (net (code "56") (name "unconnected-(U2-P-VOUT_2-Pad18)") (class "Default")
      (node (ref "U2-P") (pin "18") (pinfunction "VOUT_2_18") (pintype "bidirectional"))
    )
    (net (code "57") (name "unconnected-(U2-P-VOUT_3-Pad19)") (class "Default")
      (node (ref "U2-P") (pin "19") (pinfunction "VOUT_3_19") (pintype "bidirectional"))
    )
    (net (code "58") (name "unconnected-(U2-P-VOUT_4-Pad20)") (class "Default")
      (node (ref "U2-P") (pin "20") (pinfunction "VOUT_4_20") (pintype "bidirectional"))
    )
  )
)
